# Schematic_Livestock_control_and_monitori.net
KiCad netlist of a schematic drawn in EasyEDA
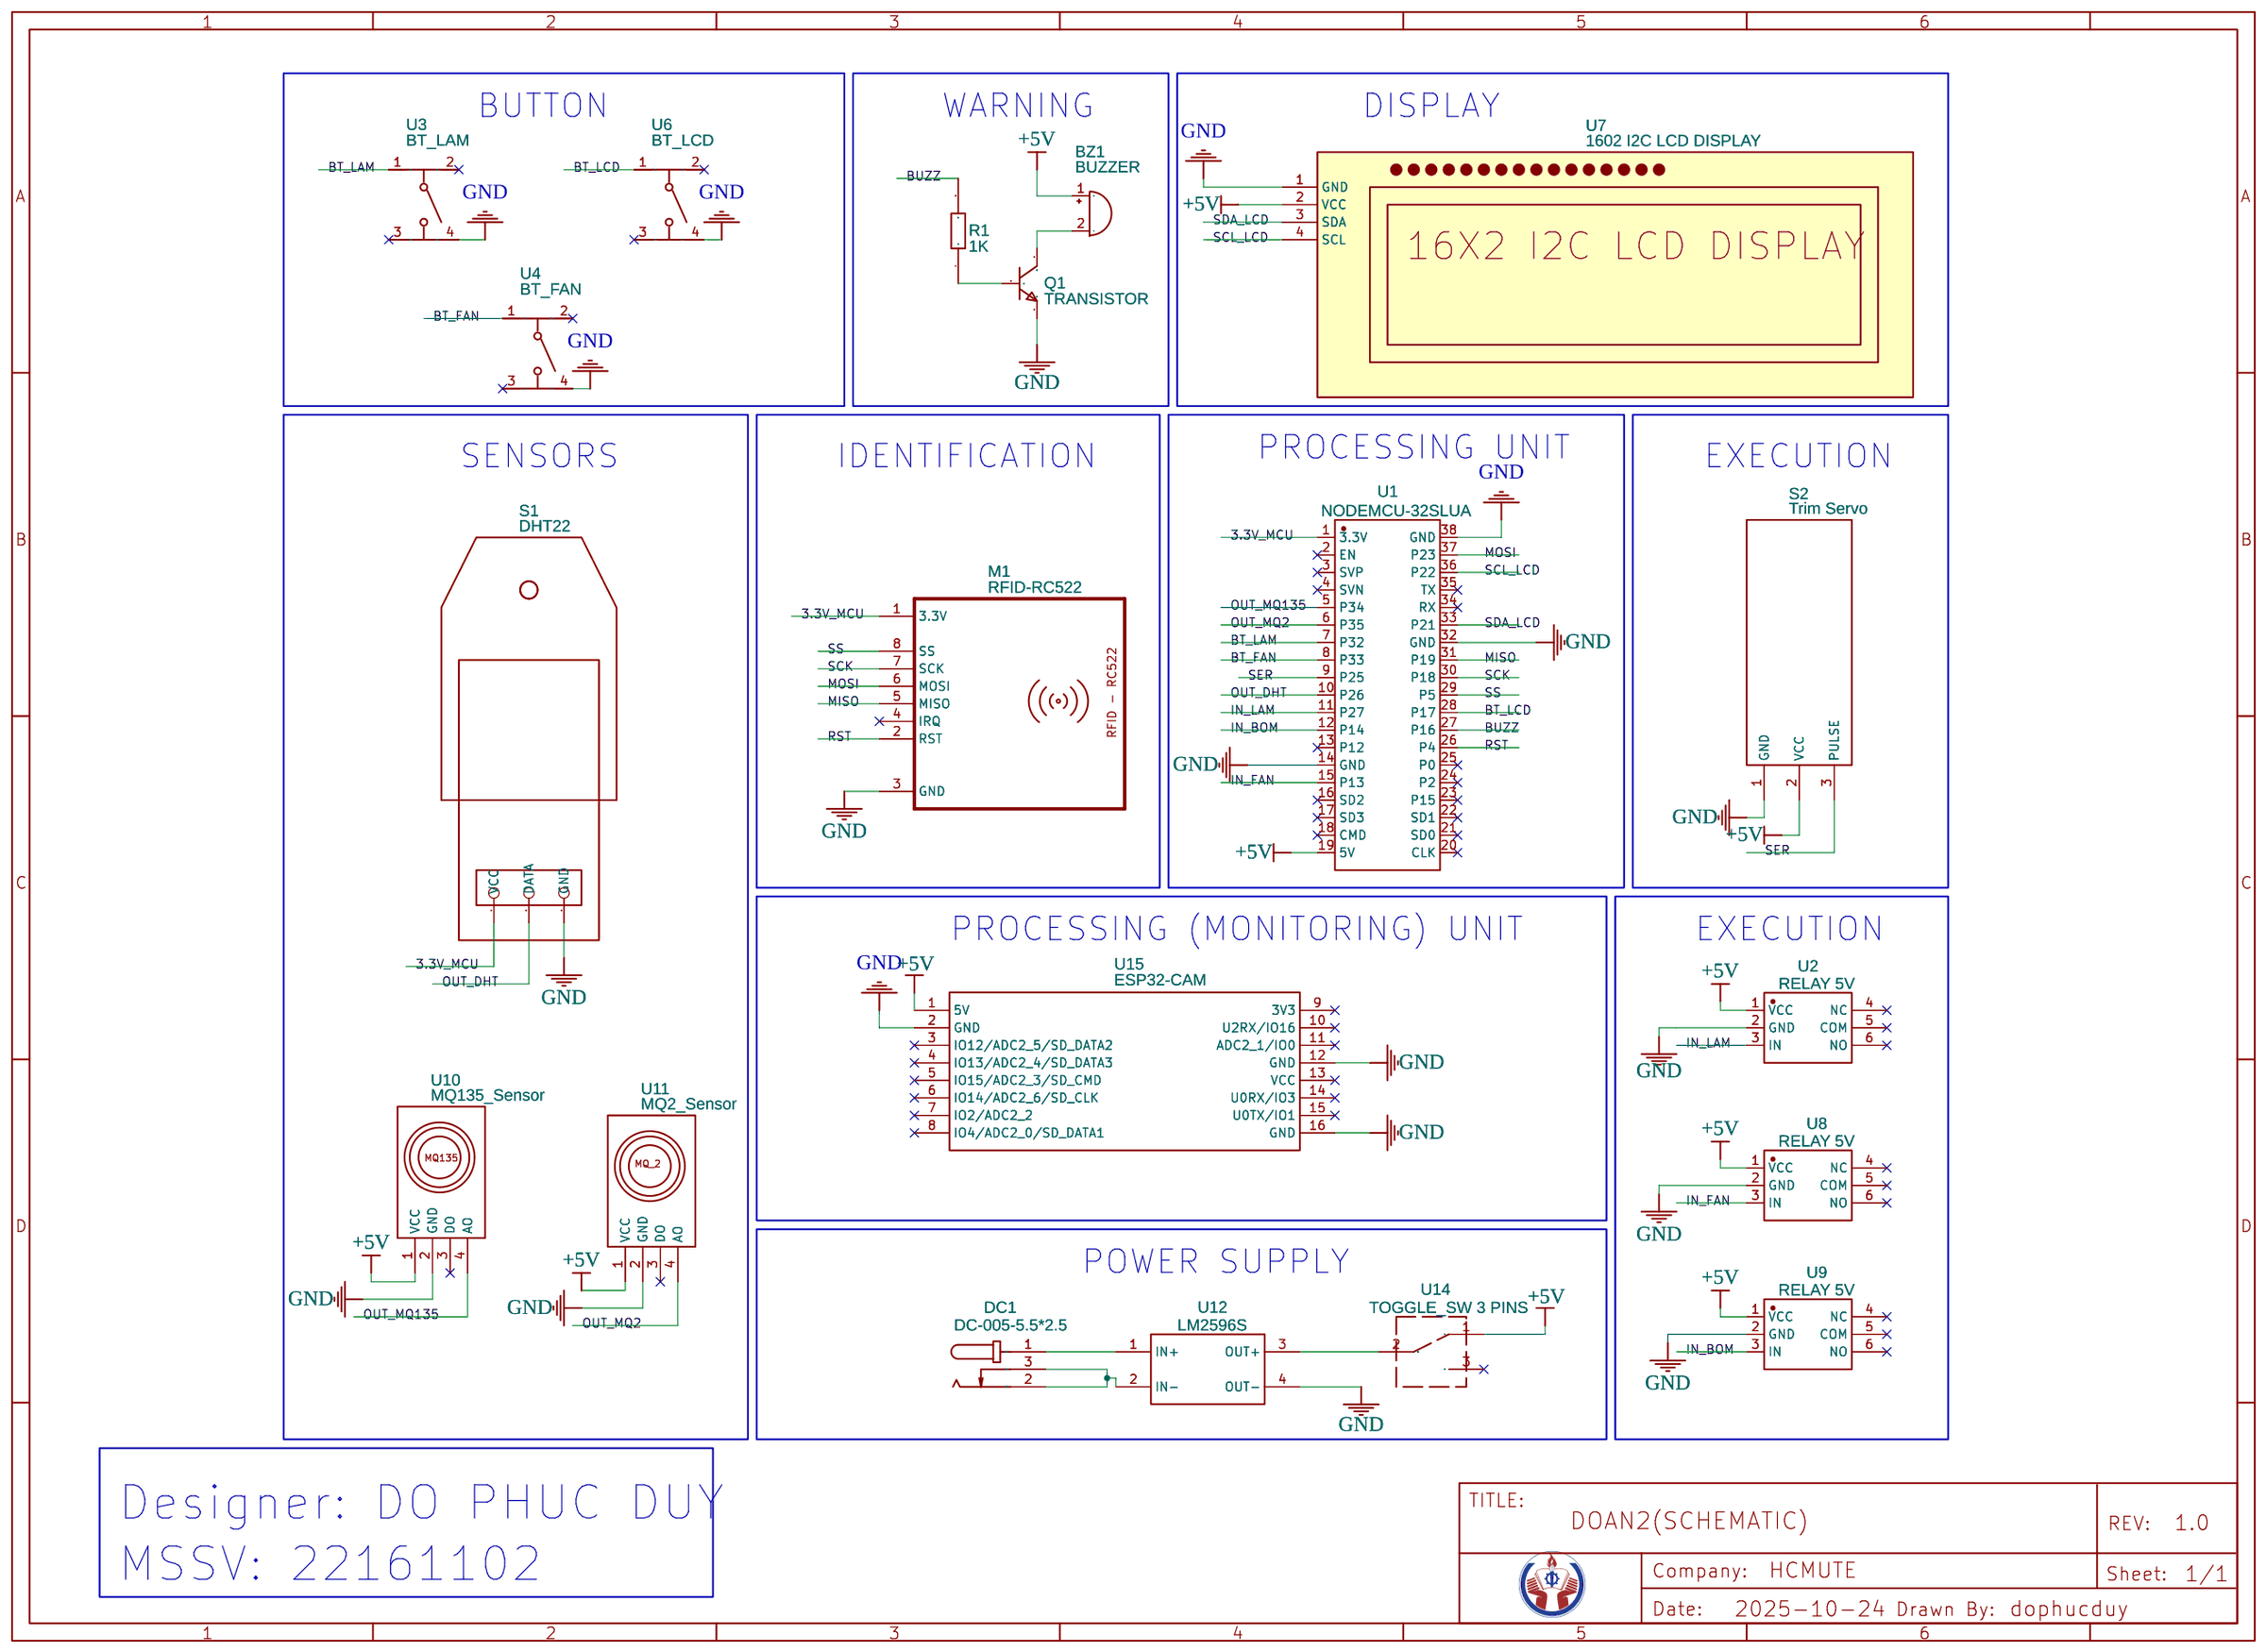
[diagram p0: schematic sheet]

(export (version "E")
  (design (tool "Eeschema 10.0.6"))
  (components
    (comp (ref "BZ1") (value "BUZZER") (libsource (lib "") (part "Device_Buzzer")))
    (comp (ref "DC1") (value "DC-005-5.5*2.5") (libsource (lib "") (part "DC-005-5.5*2.5")))
    (comp (ref "M1") (value "RFID-RC522") (libsource (lib "") (part "RFID-RC522_ARUN COPY")))
    (comp (ref "Q1")
      (value "TRANSISTOR")
      (fields (field (name "Manufacturer Part") "2N4401") (field (name "Manufacturer") "SEMTECH"))
      (libsource (lib "") (part "TRANSISTOR_ALI"))
    )
    (comp (ref "R1")
      (value "1K")
      (fields (field (name "Manufacturer Part") "MOR01SJ0101A10") (field (name "Manufacturer") "Multicomp"))
      (libsource (lib "") (part "Resistor for Asignment(long)"))
    )
    (comp (ref "S1") (value "DHT22") (libsource (lib "") (part "DHT22")))
    (comp (ref "S2") (value "Trim Servo") (libsource (lib "") (part "RC-Servo-Connector")))
    (comp (ref "U1")
      (value "NODEMCU-32SLUA")
      (fields
        (field (name "Manufacturer Part") "NodeMCU-32SLua")
        (field (name "Manufacturer") "Ai-Thinker(安信可)")
      )
      (libsource (lib "") (part "NODEMCU-32SLUA"))
    )
    (comp (ref "U2")
      (value "RELAY 5V")
      (fields (field (name "Manufacturer Part") "Monday Kids") (field (name "Manufacturer") "China"))
      (libsource (lib "") (part "VN-5V 1 CHANNEL RELAY H/L OPTO COPY COPY"))
    )
    (comp (ref "U3")
      (value "BT_LAM")
      (fields
        (field (name "Manufacturer Part") "Switch,6*6*6Plastic head,260G, 0.25mm,Straight line")
        (field (name "Manufacturer") "BBJ")
      )
      (libsource (lib "") (part "Button-6x6x6mm"))
    )
    (comp (ref "U4")
      (value "BT_FAN")
      (fields
        (field (name "Manufacturer Part") "Switch,6*6*6Plastic head,260G, 0.25mm,Straight line")
        (field (name "Manufacturer") "BBJ")
      )
      (libsource (lib "") (part "Button-6x6x6mm"))
    )
    (comp (ref "U6")
      (value "BT_LCD")
      (fields
        (field (name "Manufacturer Part") "Switch,6*6*6Plastic head,260G, 0.25mm,Straight line")
        (field (name "Manufacturer") "BBJ")
      )
      (libsource (lib "") (part "Button-6x6x6mm"))
    )
    (comp (ref "U7") (value "1602 I2C LCD DISPLAY") (libsource (lib "") (part "1602 I2C LCD DISPLAY")))
    (comp (ref "U8")
      (value "RELAY 5V")
      (fields (field (name "Manufacturer Part") "Monday Kids") (field (name "Manufacturer") "China"))
      (libsource (lib "") (part "VN-5V 1 CHANNEL RELAY H/L OPTO COPY COPY"))
    )
    (comp (ref "U9")
      (value "RELAY 5V")
      (fields (field (name "Manufacturer Part") "Monday Kids") (field (name "Manufacturer") "China"))
      (libsource (lib "") (part "VN-5V 1 CHANNEL RELAY H/L OPTO COPY COPY"))
    )
    (comp (ref "U10") (value "MQ135_Sensor") (libsource (lib "") (part "SCHLIB_MQ135_Sensor_2022-02-27_1")))
    (comp (ref "U11") (value "MQ2_Sensor") (libsource (lib "") (part "SCHLIB_MQ135_Sensor_2022-02-27")))
    (comp (ref "U12") (value "LM2596S") (libsource (lib "") (part "BuckConverters_LM2596_Adj")))
    (comp (ref "U14") (value "TOGGLE_SW 3 PINS") (libsource (lib "") (part "TOGGLE SWITCH 3 PINS")))
    (comp (ref "U15") (value "ESP32-CAM") (libsource (lib "") (part "ESP32-CAM")))
  )
  (nets
    (net (code "1") (name "+5V") (class "Default")
      (node (ref "BZ1") (pin "1") (pinfunction "+_1") (pintype "unspecified"))
      (node (ref "S2") (pin "2") (pinfunction "VCC_2") (pintype "unspecified"))
      (node (ref "U1") (pin "19") (pinfunction "5V_19") (pintype "unspecified"))
      (node (ref "U10") (pin "1") (pinfunction "VCC_1") (pintype "unspecified"))
      (node (ref "U11") (pin "1") (pinfunction "VCC_1") (pintype "unspecified"))
      (node (ref "U14") (pin "1") (pinfunction "1_1") (pintype "unspecified"))
      (node (ref "U15") (pin "1") (pinfunction "5V_1") (pintype "passive"))
      (node (ref "U2") (pin "1") (pinfunction "VCC_1") (pintype "unspecified"))
      (node (ref "U7") (pin "2") (pinfunction "VCC_2") (pintype "unspecified"))
      (node (ref "U8") (pin "1") (pinfunction "VCC_1") (pintype "unspecified"))
      (node (ref "U9") (pin "1") (pinfunction "VCC_1") (pintype "unspecified"))
    )
    (net (code "2") (name "/3.3V_MCU") (class "Default")
      (node (ref "M1") (pin "1") (pinfunction "3.3V_1") (pintype "unspecified"))
      (node (ref "S1") (pin "1") (pinfunction "VCC_1") (pintype "unspecified"))
      (node (ref "U1") (pin "1") (pinfunction "3.3V_1") (pintype "unspecified"))
    )
    (net (code "3") (name "/BT_FAN") (class "Default")
      (node (ref "U1") (pin "8") (pinfunction "P33_8") (pintype "unspecified"))
      (node (ref "U4") (pin "1") (pinfunction "1_1") (pintype "unspecified"))
    )
    (net (code "4") (name "/BT_LAM") (class "Default")
      (node (ref "U1") (pin "7") (pinfunction "P32_7") (pintype "unspecified"))
      (node (ref "U3") (pin "1") (pinfunction "1_1") (pintype "unspecified"))
    )
    (net (code "5") (name "/BT_LCD") (class "Default")
      (node (ref "U1") (pin "28") (pinfunction "P17_28") (pintype "unspecified"))
      (node (ref "U6") (pin "1") (pinfunction "1_1") (pintype "unspecified"))
    )
    (net (code "6") (name "/BUZZ") (class "Default")
      (node (ref "R1") (pin "2") (pinfunction "2_2") (pintype "unspecified"))
      (node (ref "U1") (pin "27") (pinfunction "P16_27") (pintype "unspecified"))
    )
    (net (code "7") (name "/IN_BOM") (class "Default")
      (node (ref "U1") (pin "12") (pinfunction "P14_12") (pintype "unspecified"))
      (node (ref "U9") (pin "3") (pinfunction "IN_3") (pintype "unspecified"))
    )
    (net (code "8") (name "/IN_FAN") (class "Default")
      (node (ref "U1") (pin "15") (pinfunction "P13_15") (pintype "unspecified"))
      (node (ref "U8") (pin "3") (pinfunction "IN_3") (pintype "unspecified"))
    )
    (net (code "9") (name "/IN_LAM") (class "Default")
      (node (ref "U1") (pin "11") (pinfunction "P27_11") (pintype "unspecified"))
      (node (ref "U2") (pin "3") (pinfunction "IN_3") (pintype "unspecified"))
    )
    (net (code "10") (name "/MISO") (class "Default")
      (node (ref "M1") (pin "5") (pinfunction "MISO_5") (pintype "unspecified"))
      (node (ref "U1") (pin "31") (pinfunction "P19_31") (pintype "unspecified"))
    )
    (net (code "11") (name "/MOSI") (class "Default")
      (node (ref "M1") (pin "6") (pinfunction "MOSI_6") (pintype "unspecified"))
      (node (ref "U1") (pin "37") (pinfunction "P23_37") (pintype "unspecified"))
    )
    (net (code "12") (name "/OUT_DHT") (class "Default")
      (node (ref "S1") (pin "2") (pinfunction "DATA_2") (pintype "unspecified"))
      (node (ref "U1") (pin "10") (pinfunction "P26_10") (pintype "unspecified"))
    )
    (net (code "13") (name "/OUT_MQ2") (class "Default")
      (node (ref "U1") (pin "6") (pinfunction "P35_6") (pintype "unspecified"))
      (node (ref "U11") (pin "4") (pinfunction "AO_4") (pintype "unspecified"))
    )
    (net (code "14") (name "/OUT_MQ135") (class "Default")
      (node (ref "U1") (pin "5") (pinfunction "P34_5") (pintype "unspecified"))
      (node (ref "U10") (pin "4") (pinfunction "AO_4") (pintype "unspecified"))
    )
    (net (code "15") (name "/RST") (class "Default")
      (node (ref "M1") (pin "2") (pinfunction "RST_2") (pintype "unspecified"))
      (node (ref "U1") (pin "26") (pinfunction "P4_26") (pintype "unspecified"))
    )
    (net (code "16") (name "/SCK") (class "Default")
      (node (ref "M1") (pin "7") (pinfunction "SCK_7") (pintype "unspecified"))
      (node (ref "U1") (pin "30") (pinfunction "P18_30") (pintype "unspecified"))
    )
    (net (code "17") (name "/SCL_LCD") (class "Default")
      (node (ref "U1") (pin "36") (pinfunction "P22_36") (pintype "unspecified"))
      (node (ref "U7") (pin "4") (pinfunction "SCL_4") (pintype "unspecified"))
    )
    (net (code "18") (name "/SDA_LCD") (class "Default")
      (node (ref "U1") (pin "33") (pinfunction "P21_33") (pintype "unspecified"))
      (node (ref "U7") (pin "3") (pinfunction "SDA_3") (pintype "unspecified"))
    )
    (net (code "19") (name "/SER") (class "Default")
      (node (ref "S2") (pin "3") (pinfunction "PULSE_3") (pintype "unspecified"))
      (node (ref "U1") (pin "9") (pinfunction "P25_9") (pintype "unspecified"))
    )
    (net (code "20") (name "/SS") (class "Default")
      (node (ref "M1") (pin "8") (pinfunction "SS_8") (pintype "unspecified"))
      (node (ref "U1") (pin "29") (pinfunction "P5_29") (pintype "unspecified"))
    )
    (net (code "21") (name "GND") (class "Default")
      (node (ref "M1") (pin "3") (pinfunction "GND_3") (pintype "unspecified"))
      (node (ref "Q1") (pin "1") (pinfunction "E_1") (pintype "unspecified"))
      (node (ref "S1") (pin "3") (pinfunction "GND_3") (pintype "unspecified"))
      (node (ref "S2") (pin "1") (pinfunction "GND_1") (pintype "unspecified"))
      (node (ref "U1") (pin "14") (pinfunction "GND_14") (pintype "unspecified"))
      (node (ref "U1") (pin "32") (pinfunction "GND_32") (pintype "unspecified"))
      (node (ref "U1") (pin "38") (pinfunction "GND_38") (pintype "unspecified"))
      (node (ref "U10") (pin "2") (pinfunction "GND_2") (pintype "unspecified"))
      (node (ref "U11") (pin "2") (pinfunction "GND_2") (pintype "unspecified"))
      (node (ref "U12") (pin "4") (pinfunction "OUT-_4") (pintype "unspecified"))
      (node (ref "U15") (pin "12") (pinfunction "GND_12") (pintype "passive"))
      (node (ref "U15") (pin "16") (pinfunction "GND_16") (pintype "passive"))
      (node (ref "U15") (pin "2") (pinfunction "GND_2") (pintype "passive"))
      (node (ref "U2") (pin "2") (pinfunction "GND_2") (pintype "unspecified"))
      (node (ref "U3") (pin "4") (pinfunction "4_4") (pintype "unspecified"))
      (node (ref "U4") (pin "4") (pinfunction "4_4") (pintype "unspecified"))
      (node (ref "U6") (pin "4") (pinfunction "4_4") (pintype "unspecified"))
      (node (ref "U7") (pin "1") (pinfunction "GND_1") (pintype "unspecified"))
      (node (ref "U8") (pin "2") (pinfunction "GND_2") (pintype "unspecified"))
      (node (ref "U9") (pin "2") (pinfunction "GND_2") (pintype "unspecified"))
    )
    (net (code "22") (name "Net-(BZ1--)") (class "Default")
      (node (ref "BZ1") (pin "2") (pinfunction "-_2") (pintype "unspecified"))
      (node (ref "Q1") (pin "3") (pinfunction "C_3") (pintype "unspecified"))
    )
    (net (code "23") (name "Net-(Q1-B)") (class "Default")
      (node (ref "Q1") (pin "2") (pinfunction "B_2") (pintype "unspecified"))
      (node (ref "R1") (pin "1") (pinfunction "1_1") (pintype "unspecified"))
    )
    (net (code "24") (name "Net-(U12-IN+)") (class "Default")
      (node (ref "DC1") (pin "1") (pinfunction "1_1") (pintype "unspecified"))
      (node (ref "U12") (pin "1") (pinfunction "IN+_1") (pintype "unspecified"))
    )
    (net (code "25") (name "Net-(U12-IN-)") (class "Default")
      (node (ref "DC1") (pin "2") (pinfunction "2_2") (pintype "unspecified"))
      (node (ref "DC1") (pin "3") (pinfunction "3_3") (pintype "unspecified"))
      (node (ref "U12") (pin "2") (pinfunction "IN-_2") (pintype "unspecified"))
    )
    (net (code "26") (name "Net-(U12-OUT+)") (class "Default")
      (node (ref "U12") (pin "3") (pinfunction "OUT+_3") (pintype "unspecified"))
      (node (ref "U14") (pin "2") (pinfunction "2_2") (pintype "unspecified"))
    )
    (net (code "27") (name "unconnected-(M1-IRQ-Pad4)") (class "Default")
      (node (ref "M1") (pin "4") (pinfunction "IRQ_4") (pintype "unspecified+no_connect"))
    )
    (net (code "28") (name "unconnected-(U1-CLK-Pad20)") (class "Default")
      (node (ref "U1") (pin "20") (pinfunction "CLK_20") (pintype "unspecified+no_connect"))
    )
    (net (code "29") (name "unconnected-(U1-CMD-Pad18)") (class "Default")
      (node (ref "U1") (pin "18") (pinfunction "CMD_18") (pintype "unspecified+no_connect"))
    )
    (net (code "30") (name "unconnected-(U1-EN-Pad2)") (class "Default")
      (node (ref "U1") (pin "2") (pinfunction "EN_2") (pintype "unspecified+no_connect"))
    )
    (net (code "31") (name "unconnected-(U1-P0-Pad25)") (class "Default")
      (node (ref "U1") (pin "25") (pinfunction "P0_25") (pintype "unspecified+no_connect"))
    )
    (net (code "32") (name "unconnected-(U1-P2-Pad24)") (class "Default")
      (node (ref "U1") (pin "24") (pinfunction "P2_24") (pintype "unspecified+no_connect"))
    )
    (net (code "33") (name "unconnected-(U1-P12-Pad13)") (class "Default")
      (node (ref "U1") (pin "13") (pinfunction "P12_13") (pintype "unspecified+no_connect"))
    )
    (net (code "34") (name "unconnected-(U1-P15-Pad23)") (class "Default")
      (node (ref "U1") (pin "23") (pinfunction "P15_23") (pintype "unspecified+no_connect"))
    )
    (net (code "35") (name "unconnected-(U1-RX-Pad34)") (class "Default")
      (node (ref "U1") (pin "34") (pinfunction "RX_34") (pintype "unspecified+no_connect"))
    )
    (net (code "36") (name "unconnected-(U1-SD0-Pad21)") (class "Default")
      (node (ref "U1") (pin "21") (pinfunction "SD0_21") (pintype "unspecified+no_connect"))
    )
    (net (code "37") (name "unconnected-(U1-SD1-Pad22)") (class "Default")
      (node (ref "U1") (pin "22") (pinfunction "SD1_22") (pintype "unspecified+no_connect"))
    )
    (net (code "38") (name "unconnected-(U1-SD2-Pad16)") (class "Default")
      (node (ref "U1") (pin "16") (pinfunction "SD2_16") (pintype "unspecified+no_connect"))
    )
    (net (code "39") (name "unconnected-(U1-SD3-Pad17)") (class "Default")
      (node (ref "U1") (pin "17") (pinfunction "SD3_17") (pintype "unspecified+no_connect"))
    )
    (net (code "40") (name "unconnected-(U1-SVN-Pad4)") (class "Default")
      (node (ref "U1") (pin "4") (pinfunction "SVN_4") (pintype "unspecified+no_connect"))
    )
    (net (code "41") (name "unconnected-(U1-SVP-Pad3)") (class "Default")
      (node (ref "U1") (pin "3") (pinfunction "SVP_3") (pintype "unspecified+no_connect"))
    )
    (net (code "42") (name "unconnected-(U1-TX-Pad35)") (class "Default")
      (node (ref "U1") (pin "35") (pinfunction "TX_35") (pintype "unspecified+no_connect"))
    )
    (net (code "43") (name "unconnected-(U2-COM-Pad5)") (class "Default")
      (node (ref "U2") (pin "5") (pinfunction "COM_5") (pintype "unspecified+no_connect"))
    )
    (net (code "44") (name "unconnected-(U2-NC-Pad4)") (class "Default")
      (node (ref "U2") (pin "4") (pinfunction "NC_4") (pintype "unspecified+no_connect"))
    )
    (net (code "45") (name "unconnected-(U2-NO-Pad6)") (class "Default")
      (node (ref "U2") (pin "6") (pinfunction "NO_6") (pintype "unspecified+no_connect"))
    )
    (net (code "46") (name "unconnected-(U3-Pad2)") (class "Default")
      (node (ref "U3") (pin "2") (pinfunction "2_2") (pintype "unspecified+no_connect"))
    )
    (net (code "47") (name "unconnected-(U3-Pad3)") (class "Default")
      (node (ref "U3") (pin "3") (pinfunction "3_3") (pintype "unspecified+no_connect"))
    )
    (net (code "48") (name "unconnected-(U4-Pad2)") (class "Default")
      (node (ref "U4") (pin "2") (pinfunction "2_2") (pintype "unspecified+no_connect"))
    )
    (net (code "49") (name "unconnected-(U4-Pad3)") (class "Default")
      (node (ref "U4") (pin "3") (pinfunction "3_3") (pintype "unspecified+no_connect"))
    )
    (net (code "50") (name "unconnected-(U6-Pad2)") (class "Default")
      (node (ref "U6") (pin "2") (pinfunction "2_2") (pintype "unspecified+no_connect"))
    )
    (net (code "51") (name "unconnected-(U6-Pad3)") (class "Default")
      (node (ref "U6") (pin "3") (pinfunction "3_3") (pintype "unspecified+no_connect"))
    )
    (net (code "52") (name "unconnected-(U8-COM-Pad5)") (class "Default")
      (node (ref "U8") (pin "5") (pinfunction "COM_5") (pintype "unspecified+no_connect"))
    )
    (net (code "53") (name "unconnected-(U8-NC-Pad4)") (class "Default")
      (node (ref "U8") (pin "4") (pinfunction "NC_4") (pintype "unspecified+no_connect"))
    )
    (net (code "54") (name "unconnected-(U8-NO-Pad6)") (class "Default")
      (node (ref "U8") (pin "6") (pinfunction "NO_6") (pintype "unspecified+no_connect"))
    )
    (net (code "55") (name "unconnected-(U9-COM-Pad5)") (class "Default")
      (node (ref "U9") (pin "5") (pinfunction "COM_5") (pintype "unspecified+no_connect"))
    )
    (net (code "56") (name "unconnected-(U9-NC-Pad4)") (class "Default")
      (node (ref "U9") (pin "4") (pinfunction "NC_4") (pintype "unspecified+no_connect"))
    )
    (net (code "57") (name "unconnected-(U9-NO-Pad6)") (class "Default")
      (node (ref "U9") (pin "6") (pinfunction "NO_6") (pintype "unspecified+no_connect"))
    )
    (net (code "58") (name "unconnected-(U10-DO-Pad3)") (class "Default")
      (node (ref "U10") (pin "3") (pinfunction "DO_3") (pintype "unspecified+no_connect"))
    )
    (net (code "59") (name "unconnected-(U11-DO-Pad3)") (class "Default")
      (node (ref "U11") (pin "3") (pinfunction "DO_3") (pintype "unspecified+no_connect"))
    )
    (net (code "60") (name "unconnected-(U14-Pad3)") (class "Default")
      (node (ref "U14") (pin "3") (pinfunction "3_3") (pintype "unspecified+no_connect"))
    )
    (net (code "61") (name "unconnected-(U15-3V3-Pad9)") (class "Default")
      (node (ref "U15") (pin "9") (pinfunction "3V3_9") (pintype "passive+no_connect"))
    )
    (net (code "62") (name "unconnected-(U15-ADC2_1{slash}IO0-Pad11)") (class "Default")
      (node (ref "U15") (pin "11") (pinfunction "ADC2_1/IO0_11") (pintype "bidirectional+no_connect"))
    )
    (net (code "63") (name "unconnected-(U15-IO2{slash}ADC2_2-Pad7)") (class "Default")
      (node (ref "U15") (pin "7") (pinfunction "IO2/ADC2_2_7") (pintype "bidirectional+no_connect"))
    )
    (net (code "64") (name "unconnected-(U15-IO4{slash}ADC2_0{slash}SD_DATA1-Pad8)") (class "Default")
      (node (ref "U15") (pin "8") (pinfunction "IO4/ADC2_0/SD_DATA1_8") (pintype "bidirectional+no_connect"))
    )
    (net (code "65") (name "unconnected-(U15-IO12{slash}ADC2_5{slash}SD_DATA2-Pad3)") (class "Default")
      (node (ref "U15") (pin "3") (pinfunction "IO12/ADC2_5/SD_DATA2_3") (pintype "bidirectional+no_connect"))
    )
    (net (code "66") (name "unconnected-(U15-IO13{slash}ADC2_4{slash}SD_DATA3-Pad4)") (class "Default")
      (node (ref "U15") (pin "4") (pinfunction "IO13/ADC2_4/SD_DATA3_4") (pintype "bidirectional+no_connect"))
    )
    (net (code "67") (name "unconnected-(U15-IO14{slash}ADC2_6{slash}SD_CLK-Pad6)") (class "Default")
      (node (ref "U15") (pin "6") (pinfunction "IO14/ADC2_6/SD_CLK_6") (pintype "bidirectional+no_connect"))
    )
    (net (code "68") (name "unconnected-(U15-IO15{slash}ADC2_3{slash}SD_CMD-Pad5)") (class "Default")
      (node (ref "U15") (pin "5") (pinfunction "IO15/ADC2_3/SD_CMD_5") (pintype "bidirectional+no_connect"))
    )
    (net (code "69") (name "unconnected-(U15-U0RX{slash}IO3-Pad14)") (class "Default")
      (node (ref "U15") (pin "14") (pinfunction "U0RX/IO3_14") (pintype "bidirectional+no_connect"))
    )
    (net (code "70") (name "unconnected-(U15-U0TX{slash}IO1-Pad15)") (class "Default")
      (node (ref "U15") (pin "15") (pinfunction "U0TX/IO1_15") (pintype "bidirectional+no_connect"))
    )
    (net (code "71") (name "unconnected-(U15-U2RX{slash}IO16-Pad10)") (class "Default")
      (node (ref "U15") (pin "10") (pinfunction "U2RX/IO16_10") (pintype "bidirectional+no_connect"))
    )
    (net (code "72") (name "unconnected-(U15-VCC-Pad13)") (class "Default")
      (node (ref "U15") (pin "13") (pinfunction "VCC_13") (pintype "passive+no_connect"))
    )
  )
)
